# PMIC.net
KiCad netlist of a schematic drawn in Altium Designer
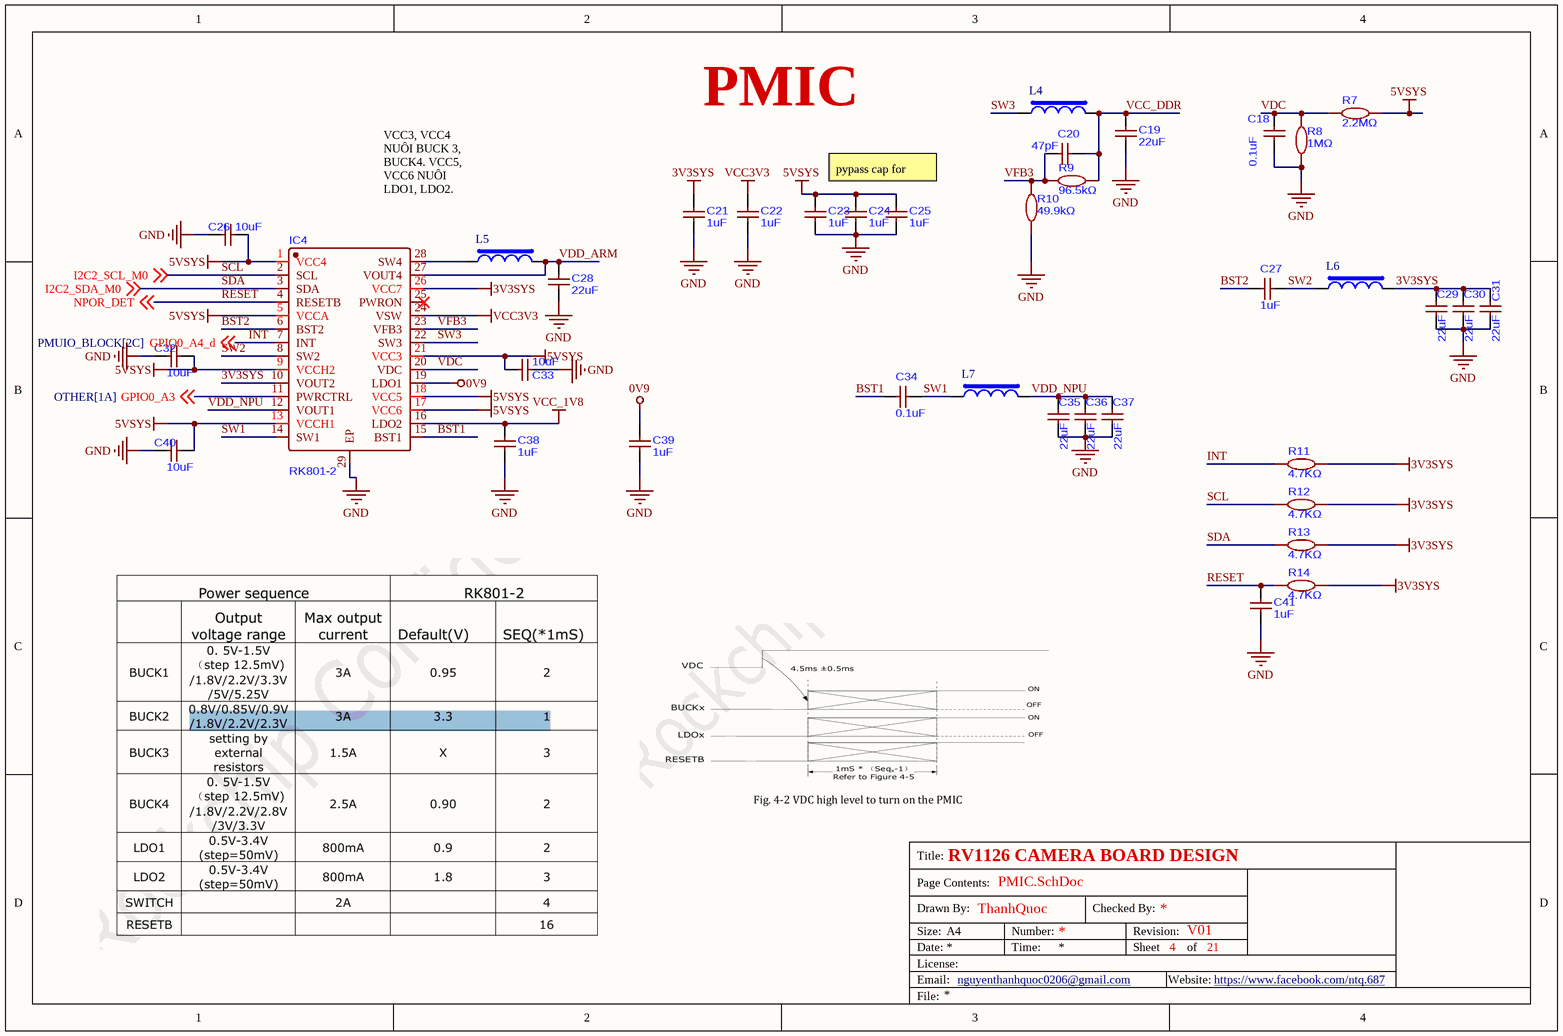
[diagram p0: PMIC.SchDoc]

(export (version "E")
  (design (tool "Eeschema 10.0.6"))
  (components
    (comp (ref "C18")
      (value "0.1uF")
      (footprint "C0201")
      (description "CAP CER 100nF 16V X5R 0201")
      (libsource (lib "Schlib1") (part "CAP_100nF-16V-10%-0201"))
    )
    (comp (ref "C19")
      (value "22uF")
      (footprint "C0603")
      (description "22uF ±20% 16V Ceramic Capacitor X5R 0603")
      (libsource (lib "Schlib1") (part "CAP_22uF-16V-20%-0603"))
    )
    (comp (ref "C20")
      (value "47pF")
      (footprint "C0201")
      (description "CAP CER  47pF ±5% 50V C0G 0201")
      (libsource (lib "Schlib1") (part "CAP_47pF-50V-5%-0201"))
    )
    (comp (ref "C21")
      (value "1uF")
      (footprint "C0201")
      (description "1uF ±10% 10V Ceramic Capacitor X5R 0201")
      (libsource (lib "Schlib1") (part "CAP_1uF-10V-10%-0201"))
    )
    (comp (ref "C22")
      (value "1uF")
      (footprint "C0201")
      (description "1uF ±10% 10V Ceramic Capacitor X5R 0201")
      (libsource (lib "Schlib1") (part "CAP_1uF-10V-10%-0201"))
    )
    (comp (ref "C23")
      (value "1uF")
      (footprint "C0201")
      (description "1uF ±10% 10V Ceramic Capacitor X5R 0201")
      (libsource (lib "Schlib1") (part "CAP_1uF-10V-10%-0201"))
    )
    (comp (ref "C24")
      (value "1uF")
      (footprint "C0201")
      (description "1uF ±10% 10V Ceramic Capacitor X5R 0201")
      (libsource (lib "Schlib1") (part "CAP_1uF-10V-10%-0201"))
    )
    (comp (ref "C25")
      (value "1uF")
      (footprint "C0201")
      (description "1uF ±10% 10V Ceramic Capacitor X5R 0201")
      (libsource (lib "Schlib1") (part "CAP_1uF-10V-10%-0201"))
    )
    (comp (ref "C26")
      (value "10uF")
      (footprint "C0402")
      (description "10µF ±20% 10V Ceramic Capacitor X5R 0402 (1005 Metric)")
      (libsource (lib "Schlib1") (part "CAP_10uF-10V-20%-0402"))
    )
    (comp (ref "C27")
      (value "1uF")
      (footprint "C0201")
      (description "1uF ±10% 10V Ceramic Capacitor X5R 0201")
      (libsource (lib "Schlib1") (part "CAP_1uF-10V-10%-0201"))
    )
    (comp (ref "C28")
      (value "22uF")
      (footprint "C0603")
      (description "22uF ±20% 16V Ceramic Capacitor X5R 0603")
      (libsource (lib "Schlib1") (part "CAP_22uF-16V-20%-0603"))
    )
    (comp (ref "C29")
      (value "22uF")
      (footprint "C0402")
      (description "22uF X5R ±20% 10V 0402 Ceramic Capacitors RoHS")
      (libsource (lib "Schlib1") (part "CAP_22uF-10V-20%-0402"))
    )
    (comp (ref "C30")
      (value "22uF")
      (footprint "C0402")
      (description "22uF X5R ±20% 10V 0402 Ceramic Capacitors RoHS")
      (libsource (lib "Schlib1") (part "CAP_22uF-10V-20%-0402"))
    )
    (comp (ref "C31")
      (value "22uF")
      (footprint "C0402")
      (description "22uF X5R ±20% 10V 0402 Ceramic Capacitors RoHS")
      (libsource (lib "Schlib1") (part "CAP_22uF-10V-20%-0402"))
    )
    (comp (ref "C32")
      (value "10uF")
      (footprint "C0402")
      (description "10µF ±20% 10V Ceramic Capacitor X5R 0402 (1005 Metric)")
      (libsource (lib "Schlib1") (part "CAP_10uF-10V-20%-0402"))
    )
    (comp (ref "C33")
      (value "10uF")
      (footprint "C0402")
      (description "10µF ±20% 10V Ceramic Capacitor X5R 0402 (1005 Metric)")
      (libsource (lib "Schlib1") (part "CAP_10uF-10V-20%-0402"))
    )
    (comp (ref "C34")
      (value "0.1uF")
      (footprint "C0201")
      (description "CAP CER 100nF 16V X5R 0201")
      (libsource (lib "Schlib1") (part "CAP_100nF-16V-10%-0201"))
    )
    (comp (ref "C35")
      (value "22uF")
      (footprint "C0402")
      (description "22uF X5R ±20% 10V 0402 Ceramic Capacitors RoHS")
      (libsource (lib "Schlib1") (part "CAP_22uF-10V-20%-0402"))
    )
    (comp (ref "C36")
      (value "22uF")
      (footprint "C0402")
      (description "22uF X5R ±20% 10V 0402 Ceramic Capacitors RoHS")
      (libsource (lib "Schlib1") (part "CAP_22uF-10V-20%-0402"))
    )
    (comp (ref "C37")
      (value "22uF")
      (footprint "C0402")
      (description "22uF X5R ±20% 10V 0402 Ceramic Capacitors RoHS")
      (libsource (lib "Schlib1") (part "CAP_22uF-10V-20%-0402"))
    )
    (comp (ref "C38")
      (value "1uF")
      (footprint "C0201")
      (description "1uF ±10% 10V Ceramic Capacitor X5R 0201")
      (libsource (lib "Schlib1") (part "CAP_1uF-10V-10%-0201"))
    )
    (comp (ref "C39")
      (value "1uF")
      (footprint "C0201")
      (description "1uF ±10% 10V Ceramic Capacitor X5R 0201")
      (libsource (lib "Schlib1") (part "CAP_1uF-10V-10%-0201"))
    )
    (comp (ref "C40")
      (value "10uF")
      (footprint "C0402")
      (description "10µF ±20% 10V Ceramic Capacitor X5R 0402 (1005 Metric)")
      (libsource (lib "Schlib1") (part "CAP_10uF-10V-20%-0402"))
    )
    (comp (ref "C41")
      (value "1uF")
      (footprint "C0201")
      (description "1uF ±10% 10V Ceramic Capacitor X5R 0201")
      (libsource (lib "Schlib1") (part "CAP_1uF-10V-10%-0201"))
    )
    (comp (ref "IC4")
      (value "RK801-2")
      (footprint "QFN-28_L4.0-W4.0-P0.40-TL-EP2.4")
      (description "I2C QFN-28-EP(4x4) Power Management - Specialized RoHS")
      (libsource (lib "Schlib1") (part "RK801-2"))
    )
    (comp (ref "L4")
      (value "FTC252012SR47MBCA")
      (footprint "IND_1008")
      (description "FIXED IND 0.47uH 6.5A 13mΩ SMD,2x2.5mm")
      (fields
        (field (name "MANUFACTURER") "Murata Electronics")
        (field (name "MANUFACTURER PART NUMBER") "DFE252010P-R47M=P2")
      )
      (libsource (lib "Schlib1") (part "IND_470nH-6.5A-20%-1008"))
    )
    (comp (ref "L5")
      (value "FTC252012SR47MBCA")
      (footprint "IND_1008")
      (description "FIXED IND 0.47uH 6.5A 13mΩ SMD,2x2.5mm")
      (fields
        (field (name "MANUFACTURER") "Murata Electronics")
        (field (name "MANUFACTURER PART NUMBER") "DFE252010P-R47M=P2")
      )
      (libsource (lib "Schlib1") (part "IND_470nH-6.5A-20%-1008"))
    )
    (comp (ref "L6")
      (value "PSTMAA252012-2R2MB")
      (footprint "IND_1008")
      (description "2.2uH Shielded Wirewound Inductor 4.1A 60mOhm Max 1008 (2520 Metric)")
      (fields
        (field (name "MANUFACTURER") "Murata Electronics")
        (field (name "MANUFACTURER PART NUMBER") "DFE252010-R47M=P2")
      )
      (libsource (lib "Schlib1") (part "IND_2.2uH-4.1A-20%-1008"))
    )
    (comp (ref "L7")
      (value "PSTMAA252012-2R2MB")
      (footprint "IND_1008")
      (description "2.2uH Shielded Wirewound Inductor 4.1A 60mOhm Max 1008 (2520 Metric)")
      (fields
        (field (name "MANUFACTURER") "Murata Electronics")
        (field (name "MANUFACTURER PART NUMBER") "DFE252010-R47M=P2")
      )
      (libsource (lib "Schlib1") (part "IND_2.2uH-4.1A-20%-1008"))
    )
    (comp (ref "R7")
      (value "2.2MΩ")
      (footprint "R0402")
      (description "RES 2.2MΩ ±1% 62.5mW 0402")
      (libsource (lib "Schlib1") (part "RES_2.2M-62.5W-1%-0402"))
    )
    (comp (ref "R8")
      (value "1MΩ")
      (footprint "R0201")
      (description "RES 1MΩ ±0.1% 50mW 0201")
      (libsource (lib "Schlib1") (part "RES_1M-50mW-0.1%-0201"))
    )
    (comp (ref "R9")
      (value "96.5kΩ")
      (footprint "R0402")
      (description "RES 96.5kΩ ±0.1% 62.5mW 0402")
      (libsource (lib "Schlib1") (part "RES_96.5K-0.1W-0.1%-0402"))
    )
    (comp (ref "R10")
      (value "49.9kΩ")
      (footprint "R0402")
      (description "RES 49.9kΩ ±0.1% 62.5mW 0402")
      (libsource (lib "Schlib1") (part "RES_49.9K-0.1W-0.1%-0402"))
    )
    (comp (ref "R11")
      (value "4.7KΩ")
      (footprint "R0201")
      (description "RES 4.7kΩ ±1% 50mW 0201")
      (libsource (lib "Schlib1") (part "RES_4.7K-50mW-1%-0201"))
    )
    (comp (ref "R12")
      (value "4.7KΩ")
      (footprint "R0201")
      (description "RES 4.7kΩ ±1% 50mW 0201")
      (libsource (lib "Schlib1") (part "RES_4.7K-50mW-1%-0201"))
    )
    (comp (ref "R13")
      (value "4.7KΩ")
      (footprint "R0201")
      (description "RES 4.7kΩ ±1% 50mW 0201")
      (libsource (lib "Schlib1") (part "RES_4.7K-50mW-1%-0201"))
    )
    (comp (ref "R14")
      (value "4.7KΩ")
      (footprint "R0201")
      (description "RES 4.7kΩ ±1% 50mW 0201")
      (libsource (lib "Schlib1") (part "RES_4.7K-50mW-1%-0201"))
    )
  )
  (nets
    (net (code "1") (name "/BST1") (class "Default")
      (node (ref "C34") (pin "1") (pinfunction "1_1") (pintype "passive"))
      (node (ref "IC4") (pin "15") (pinfunction "BST1_15") (pintype "passive"))
    )
    (net (code "2") (name "/BST2") (class "Default")
      (node (ref "C27") (pin "2") (pinfunction "2_2") (pintype "passive"))
      (node (ref "IC4") (pin "6") (pinfunction "BST2_6") (pintype "passive"))
    )
    (net (code "3") (name "/SW1") (class "Default")
      (node (ref "C34") (pin "2") (pinfunction "2_2") (pintype "passive"))
      (node (ref "IC4") (pin "14") (pinfunction "SW1_14") (pintype "passive"))
      (node (ref "L7") (pin "1") (pinfunction "1_1") (pintype "passive"))
    )
    (net (code "4") (name "/SW2") (class "Default")
      (node (ref "C27") (pin "1") (pinfunction "1_1") (pintype "passive"))
      (node (ref "IC4") (pin "8") (pinfunction "SW2_8") (pintype "passive"))
      (node (ref "L6") (pin "1") (pinfunction "1_1") (pintype "passive"))
    )
    (net (code "5") (name "/SW3") (class "Default")
      (node (ref "IC4") (pin "22") (pinfunction "SW3_22") (pintype "passive"))
      (node (ref "L4") (pin "1") (pinfunction "1_1") (pintype "passive"))
    )
    (net (code "6") (name "/VCC_DDR") (class "Default")
      (node (ref "C19") (pin "2") (pinfunction "2_2") (pintype "passive"))
      (node (ref "C20") (pin "2") (pinfunction "2_2") (pintype "passive"))
      (node (ref "L4") (pin "2") (pinfunction "2_2") (pintype "passive"))
      (node (ref "R9") (pin "2") (pinfunction "2_2") (pintype "passive"))
    )
    (net (code "7") (name "/VDC") (class "Default")
      (node (ref "C18") (pin "2") (pinfunction "2_2") (pintype "passive"))
      (node (ref "IC4") (pin "20") (pinfunction "VDC_20") (pintype "passive"))
      (node (ref "R7") (pin "1") (pinfunction "1_1") (pintype "passive"))
      (node (ref "R8") (pin "2") (pinfunction "2_2") (pintype "passive"))
    )
    (net (code "8") (name "/VDD_ARM") (class "Default")
      (node (ref "C28") (pin "2") (pinfunction "2_2") (pintype "passive"))
      (node (ref "IC4") (pin "27") (pinfunction "VOUT4_27") (pintype "passive"))
      (node (ref "L5") (pin "2") (pinfunction "2_2") (pintype "passive"))
    )
    (net (code "9") (name "/VDD_NPU") (class "Default")
      (node (ref "C35") (pin "2") (pinfunction "2_2") (pintype "passive"))
      (node (ref "C36") (pin "2") (pinfunction "2_2") (pintype "passive"))
      (node (ref "C37") (pin "2") (pinfunction "2_2") (pintype "passive"))
      (node (ref "IC4") (pin "12") (pinfunction "VOUT1_12") (pintype "passive"))
      (node (ref "L7") (pin "2") (pinfunction "2_2") (pintype "passive"))
    )
    (net (code "10") (name "/VFB3") (class "Default")
      (node (ref "C20") (pin "1") (pinfunction "1_1") (pintype "passive"))
      (node (ref "IC4") (pin "23") (pinfunction "VFB3_23") (pintype "passive"))
      (node (ref "R10") (pin "2") (pinfunction "2_2") (pintype "passive"))
      (node (ref "R9") (pin "1") (pinfunction "1_1") (pintype "passive"))
    )
    (net (code "11") (name "0V9") (class "Default")
      (node (ref "C39") (pin "2") (pinfunction "2_2") (pintype "passive"))
      (node (ref "IC4") (pin "19") (pinfunction "LDO1_19") (pintype "passive"))
    )
    (net (code "12") (name "3V3SYS") (class "Default")
      (node (ref "C21") (pin "2") (pinfunction "2_2") (pintype "passive"))
      (node (ref "C29") (pin "2") (pinfunction "2_2") (pintype "passive"))
      (node (ref "C30") (pin "2") (pinfunction "2_2") (pintype "passive"))
      (node (ref "C31") (pin "2") (pinfunction "2_2") (pintype "passive"))
      (node (ref "IC4") (pin "10") (pinfunction "VOUT2_10") (pintype "passive"))
      (node (ref "IC4") (pin "26") (pinfunction "VCC7_26") (pintype "passive"))
      (node (ref "L6") (pin "2") (pinfunction "2_2") (pintype "passive"))
      (node (ref "R11") (pin "2") (pinfunction "2_2") (pintype "passive"))
      (node (ref "R12") (pin "2") (pinfunction "2_2") (pintype "passive"))
      (node (ref "R13") (pin "2") (pinfunction "2_2") (pintype "passive"))
      (node (ref "R14") (pin "2") (pinfunction "2_2") (pintype "passive"))
    )
    (net (code "13") (name "5VSYS") (class "Default")
      (node (ref "C23") (pin "2") (pinfunction "2_2") (pintype "passive"))
      (node (ref "C24") (pin "2") (pinfunction "2_2") (pintype "passive"))
      (node (ref "C25") (pin "2") (pinfunction "2_2") (pintype "passive"))
      (node (ref "C26") (pin "2") (pinfunction "2_2") (pintype "passive"))
      (node (ref "C32") (pin "1") (pinfunction "1_1") (pintype "passive"))
      (node (ref "C33") (pin "2") (pinfunction "2_2") (pintype "passive"))
      (node (ref "C40") (pin "2") (pinfunction "2_2") (pintype "passive"))
      (node (ref "IC4") (pin "1") (pinfunction "VCC4_1") (pintype "passive"))
      (node (ref "IC4") (pin "13") (pinfunction "VCCH1_13") (pintype "passive"))
      (node (ref "IC4") (pin "17") (pinfunction "VCC6_17") (pintype "passive"))
      (node (ref "IC4") (pin "18") (pinfunction "VCC5_18") (pintype "passive"))
      (node (ref "IC4") (pin "21") (pinfunction "VCC3_21") (pintype "passive"))
      (node (ref "IC4") (pin "5") (pinfunction "VCCA_5") (pintype "passive"))
      (node (ref "IC4") (pin "9") (pinfunction "VCCH2_9") (pintype "passive"))
      (node (ref "R7") (pin "2") (pinfunction "2_2") (pintype "passive"))
    )
    (net (code "14") (name "GND") (class "Default")
      (node (ref "C18") (pin "1") (pinfunction "1_1") (pintype "passive"))
      (node (ref "C19") (pin "1") (pinfunction "1_1") (pintype "passive"))
      (node (ref "C21") (pin "1") (pinfunction "1_1") (pintype "passive"))
      (node (ref "C22") (pin "1") (pinfunction "1_1") (pintype "passive"))
      (node (ref "C23") (pin "1") (pinfunction "1_1") (pintype "passive"))
      (node (ref "C24") (pin "1") (pinfunction "1_1") (pintype "passive"))
      (node (ref "C25") (pin "1") (pinfunction "1_1") (pintype "passive"))
      (node (ref "C26") (pin "1") (pinfunction "1_1") (pintype "passive"))
      (node (ref "C28") (pin "1") (pinfunction "1_1") (pintype "passive"))
      (node (ref "C29") (pin "1") (pinfunction "1_1") (pintype "passive"))
      (node (ref "C30") (pin "1") (pinfunction "1_1") (pintype "passive"))
      (node (ref "C31") (pin "1") (pinfunction "1_1") (pintype "passive"))
      (node (ref "C32") (pin "2") (pinfunction "2_2") (pintype "passive"))
      (node (ref "C33") (pin "1") (pinfunction "1_1") (pintype "passive"))
      (node (ref "C35") (pin "1") (pinfunction "1_1") (pintype "passive"))
      (node (ref "C36") (pin "1") (pinfunction "1_1") (pintype "passive"))
      (node (ref "C37") (pin "1") (pinfunction "1_1") (pintype "passive"))
      (node (ref "C38") (pin "1") (pinfunction "1_1") (pintype "passive"))
      (node (ref "C39") (pin "1") (pinfunction "1_1") (pintype "passive"))
      (node (ref "C40") (pin "1") (pinfunction "1_1") (pintype "passive"))
      (node (ref "C41") (pin "1") (pinfunction "1_1") (pintype "passive"))
      (node (ref "IC4") (pin "29") (pinfunction "EP_29") (pintype "passive"))
      (node (ref "R10") (pin "1") (pinfunction "1_1") (pintype "passive"))
      (node (ref "R8") (pin "1") (pinfunction "1_1") (pintype "passive"))
    )
    (net (code "15") (name "GPIO0_A3") (class "Default")
      (node (ref "IC4") (pin "11") (pinfunction "PWRCTRL_11") (pintype "passive"))
    )
    (net (code "16") (name "GPIO0_A4_d") (class "Default")
      (node (ref "IC4") (pin "7") (pinfunction "INT_7") (pintype "passive"))
      (node (ref "R11") (pin "1") (pinfunction "1_1") (pintype "passive"))
    )
    (net (code "17") (name "I2C2_SCL_M0") (class "Default")
      (node (ref "IC4") (pin "2") (pinfunction "SCL_2") (pintype "passive"))
      (node (ref "R12") (pin "1") (pinfunction "1_1") (pintype "passive"))
    )
    (net (code "18") (name "I2C2_SDA_M0") (class "Default")
      (node (ref "IC4") (pin "3") (pinfunction "SDA_3") (pintype "passive"))
      (node (ref "R13") (pin "1") (pinfunction "1_1") (pintype "passive"))
    )
    (net (code "19") (name "NPOR_DET") (class "Default")
      (node (ref "C41") (pin "2") (pinfunction "2_2") (pintype "passive"))
      (node (ref "IC4") (pin "4") (pinfunction "RESETB_4") (pintype "passive"))
      (node (ref "R14") (pin "1") (pinfunction "1_1") (pintype "passive"))
    )
    (net (code "20") (name "Net-(IC4-SW4)") (class "Default")
      (node (ref "IC4") (pin "28") (pinfunction "SW4_28") (pintype "passive"))
      (node (ref "L5") (pin "1") (pinfunction "1_1") (pintype "passive"))
    )
    (net (code "21") (name "VCC3V3") (class "Default")
      (node (ref "C22") (pin "2") (pinfunction "2_2") (pintype "passive"))
      (node (ref "IC4") (pin "24") (pinfunction "VSW_24") (pintype "passive"))
    )
    (net (code "22") (name "VCC_1V8") (class "Default")
      (node (ref "C38") (pin "2") (pinfunction "2_2") (pintype "passive"))
      (node (ref "IC4") (pin "16") (pinfunction "LDO2_16") (pintype "passive"))
    )
    (net (code "23") (name "unconnected-(IC4-PWRON-Pad25)") (class "Default")
      (node (ref "IC4") (pin "25") (pinfunction "PWRON_25") (pintype "passive+no_connect"))
    )
  )
)
